# Sheet1.net
KiCad netlist of a schematic drawn in Altium Designer
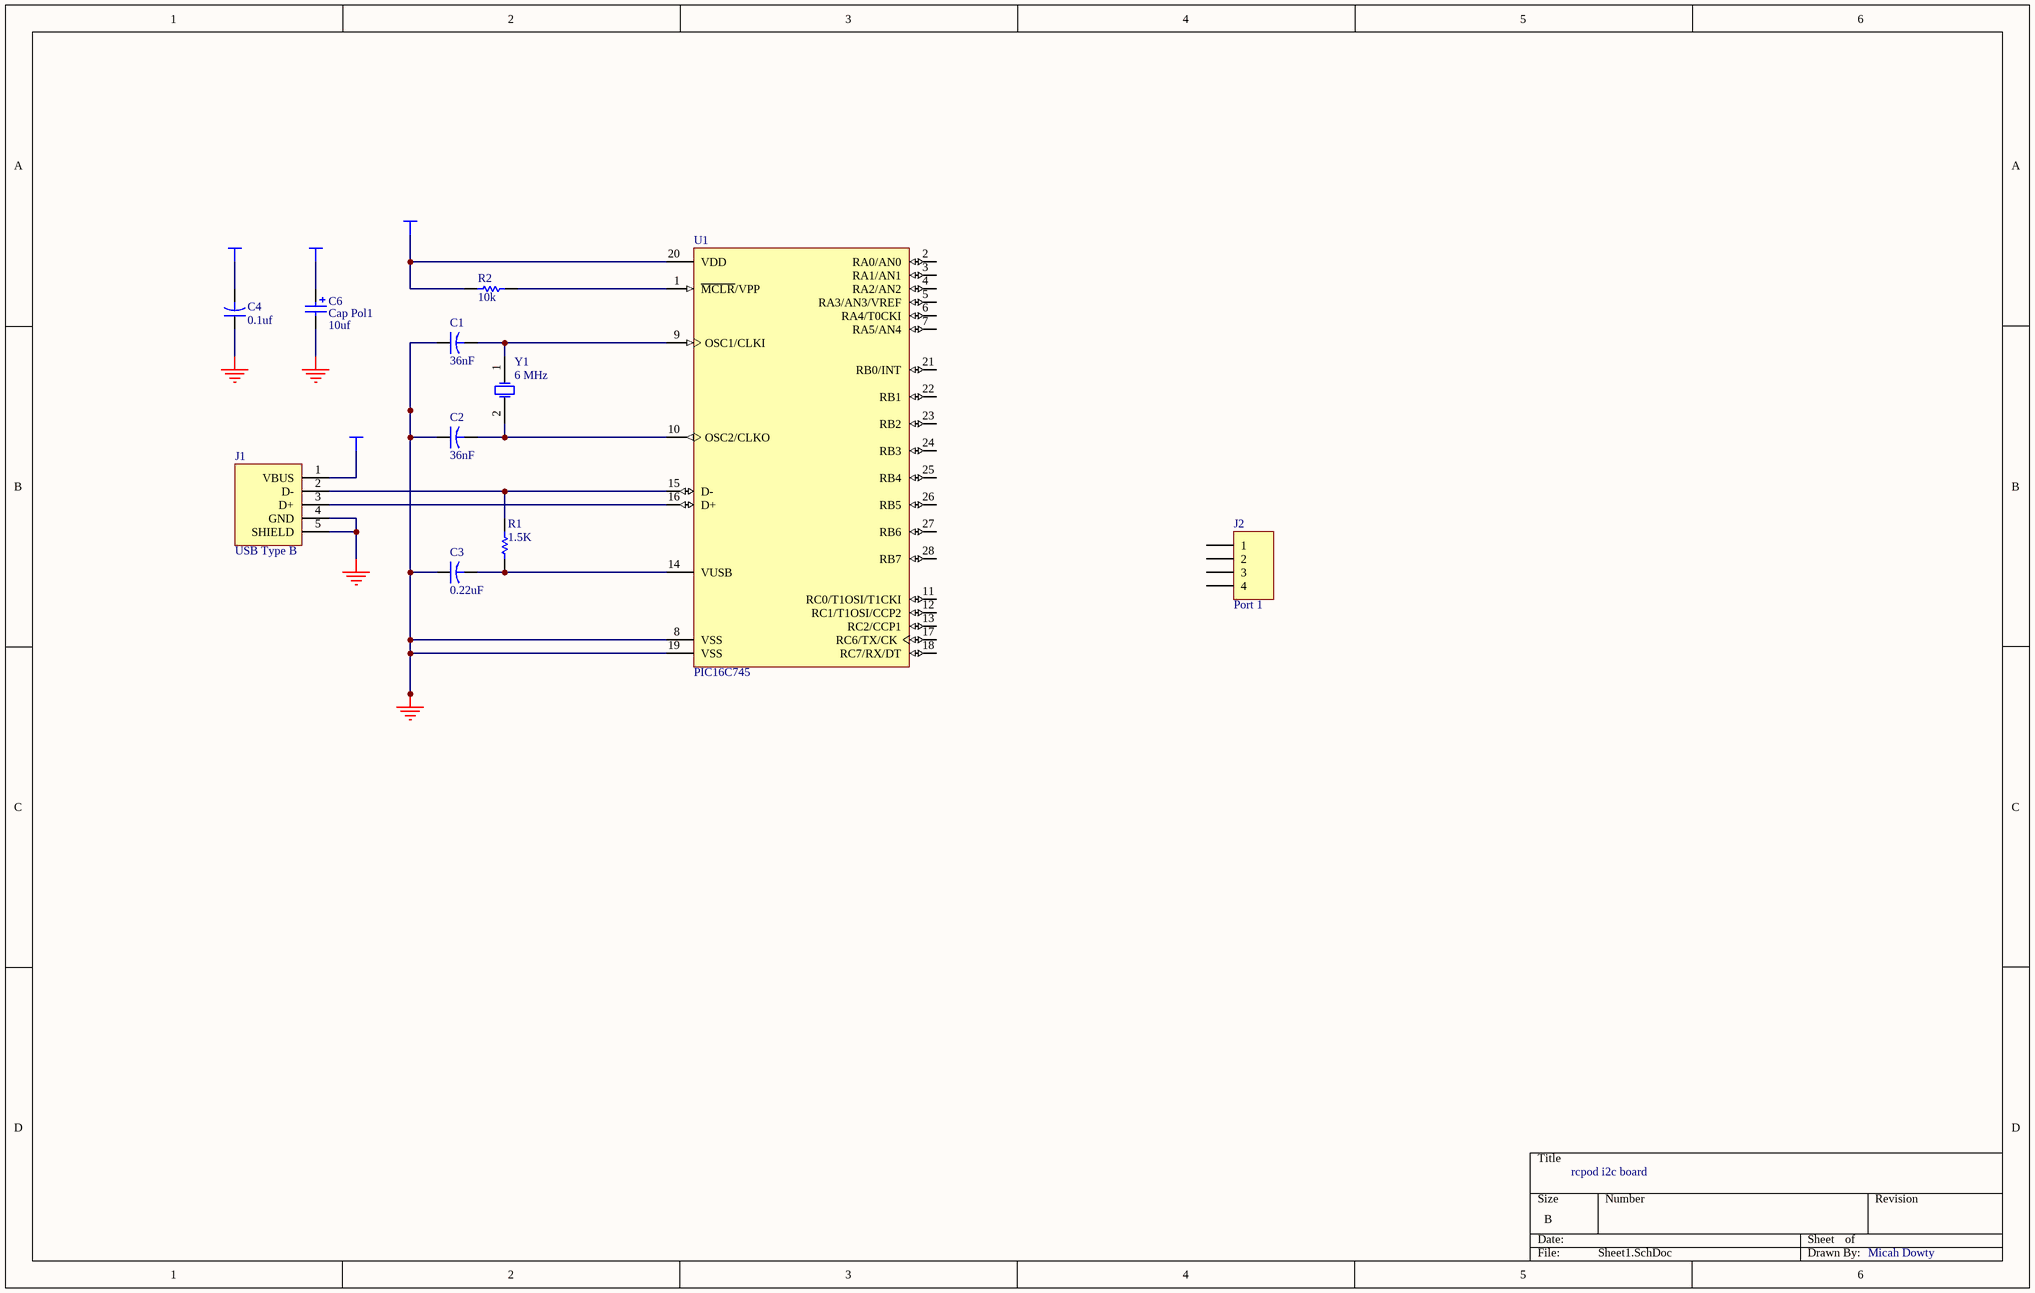
[diagram p0: Sheet1.SchDoc]

(export (version "E")
  (design (tool "Eeschema 10.0.6"))
  (components
    (comp (ref "C1")
      (value "Cap2")
      (footprint "CAPR5-4X5")
      (description "Capacitor")
      (fields
        (field (name "MANUFACTURER") "Generic Components")
        (field (name "ALTIUM_VALUE") "36nF")
        (field (name "PUBLISHER") "Altium Limited")
      )
      (libsource (lib "Miscellaneous Devices") (part "Cap2"))
    )
    (comp (ref "C2")
      (value "Cap2")
      (footprint "CAPR5-4X5")
      (description "Capacitor")
      (fields
        (field (name "MANUFACTURER") "Generic Components")
        (field (name "ALTIUM_VALUE") "36nF")
        (field (name "PUBLISHER") "Altium Limited")
      )
      (libsource (lib "Miscellaneous Devices") (part "Cap2"))
    )
    (comp (ref "C3")
      (value "0.22uF")
      (footprint "CAPR5-4X5")
      (description "Capacitor")
      (fields (field (name "MANUFACTURER") "Generic Components") (field (name "PUBLISHER") "Altium Limited"))
      (libsource (lib "Miscellaneous Devices") (part "Cap2"))
    )
    (comp (ref "C4")
      (value "0.1uf")
      (footprint "CAPR5-4X5")
      (description "Capacitor")
      (fields (field (name "MANUFACTURER") "Generic Components") (field (name "PUBLISHER") "Altium Limited"))
      (libsource (lib "Miscellaneous Devices") (part "Cap2"))
    )
    (comp (ref "C6")
      (value "Cap Pol1")
      (footprint "CAP-EE-1")
      (description "Polarized Capacitor (Radial)")
      (fields
        (field (name "MANUFACTURER") "Generic Components")
        (field (name "ALTIUM_VALUE") "10uf")
        (field (name "PUBLISHER") "Altium Limited")
      )
      (libsource (lib "Miscellaneous Devices") (part "Cap Pol1"))
    )
    (comp (ref "J1")
      (value "USB")
      (footprint "USB-TYPEB")
      (description "Header, 4-Pin")
      (fields (field (name "MANUFACTURER") "Generic Components") (field (name "PUBLISHER") "Altium Limited"))
      (libsource (lib "parts") (part "USB Type B"))
    )
    (comp (ref "J2")
      (value "Port 1")
      (footprint "HDR1X4")
      (description "Header, 4-Pin")
      (fields (field (name "MANUFACTURER") "Generic Components") (field (name "PUBLISHER") "Altium Limited"))
      (libsource (lib "Miscellaneous Connectors") (part "Header 4"))
    )
    (comp (ref "R1")
      (value "Res1")
      (footprint "AXIAL-0.3")
      (description "Resistor")
      (fields
        (field (name "MANUFACTURER") "Generic Components")
        (field (name "ALTIUM_VALUE") "1.5K")
        (field (name "PUBLISHER") "Altium Limited")
      )
      (libsource (lib "Miscellaneous Devices") (part "Res1"))
    )
    (comp (ref "R2")
      (value "Res1")
      (footprint "AXIAL-0.3")
      (description "Resistor")
      (fields
        (field (name "MANUFACTURER") "Generic Components")
        (field (name "ALTIUM_VALUE") "10k")
        (field (name "PUBLISHER") "Altium Limited")
      )
      (libsource (lib "Miscellaneous Devices") (part "Res1"))
    )
    (comp (ref "U1")
      (value "~")
      (footprint "DIP-28")
      (description "EPROM-Based 8-Bit CMOS Microcontroller with USB")
      (fields (field (name "MANUFACTURER") "Microchip"))
      (libsource (lib "parts") (part "PIC16C745"))
    )
    (comp (ref "Y1")
      (value "6 MHz")
      (footprint "BCY-W2/E4.7")
      (description "Crystal Oscillator")
      (fields (field (name "MANUFACTURER") "Generic Components") (field (name "PUBLISHER") "Altium Limited"))
      (libsource (lib "Miscellaneous Devices") (part "XTAL"))
    )
  )
  (nets
    (net (code "1") (name "GND") (class "Default")
      (node (ref "C1") (pin "1") (pinfunction "1_1") (pintype "passive"))
      (node (ref "C2") (pin "1") (pinfunction "1_1") (pintype "passive"))
      (node (ref "C3") (pin "1") (pinfunction "1_1") (pintype "passive"))
      (node (ref "C4") (pin "1") (pinfunction "1_1") (pintype "passive"))
      (node (ref "C6") (pin "2") (pinfunction "2_2") (pintype "passive"))
      (node (ref "J1") (pin "4") (pinfunction "GND_4") (pintype "passive"))
      (node (ref "J1") (pin "5") (pinfunction "SHIELD_5") (pintype "power_in"))
      (node (ref "U1") (pin "19") (pinfunction "VSS_19") (pintype "power_in"))
      (node (ref "U1") (pin "8") (pinfunction "VSS_8") (pintype "power_in"))
    )
    (net (code "2") (name "Net-(J1-D+)") (class "Default")
      (node (ref "J1") (pin "3") (pinfunction "D+_3") (pintype "passive"))
      (node (ref "U1") (pin "16") (pinfunction "D+_16") (pintype "bidirectional"))
    )
    (net (code "3") (name "Net-(J1-D-)") (class "Default")
      (node (ref "J1") (pin "2") (pinfunction "D-_2") (pintype "passive"))
      (node (ref "R1") (pin "2") (pinfunction "2_2") (pintype "passive"))
      (node (ref "U1") (pin "15") (pinfunction "D-_15") (pintype "bidirectional"))
    )
    (net (code "4") (name "Net-(U1-OSC1{slash}CLKI)") (class "Default")
      (node (ref "C1") (pin "2") (pinfunction "2_2") (pintype "passive"))
      (node (ref "U1") (pin "9") (pinfunction "OSC1/CLKI_9") (pintype "input"))
      (node (ref "Y1") (pin "1") (pinfunction "OSC1_1") (pintype "passive"))
    )
    (net (code "5") (name "Net-(U1-OSC2{slash}CLKO)") (class "Default")
      (node (ref "C2") (pin "2") (pinfunction "2_2") (pintype "passive"))
      (node (ref "U1") (pin "10") (pinfunction "OSC2/CLKO_10") (pintype "output"))
      (node (ref "Y1") (pin "2") (pinfunction "OSC2_2") (pintype "passive"))
    )
    (net (code "6") (name "Net-(U1-VUSB)") (class "Default")
      (node (ref "C3") (pin "2") (pinfunction "2_2") (pintype "passive"))
      (node (ref "R1") (pin "1") (pinfunction "1_1") (pintype "passive"))
      (node (ref "U1") (pin "14") (pinfunction "VUSB_14") (pintype "power_in"))
    )
    (net (code "7") (name "Net-(U1-~{MCLR}{slash}VPP)") (class "Default")
      (node (ref "R2") (pin "1") (pinfunction "1_1") (pintype "passive"))
      (node (ref "U1") (pin "1") (pinfunction "~{MCLR}/VPP_1") (pintype "input"))
    )
    (net (code "8") (name "VCC") (class "Default")
      (node (ref "C4") (pin "2") (pinfunction "2_2") (pintype "passive"))
      (node (ref "C6") (pin "1") (pinfunction "1_1") (pintype "passive"))
      (node (ref "J1") (pin "1") (pinfunction "VBUS_1") (pintype "passive"))
      (node (ref "R2") (pin "2") (pinfunction "2_2") (pintype "passive"))
      (node (ref "U1") (pin "20") (pinfunction "VDD_20") (pintype "power_in"))
    )
    (net (code "9") (name "unconnected-(J2-Pad1)") (class "Default")
      (node (ref "J2") (pin "1") (pinfunction "1_1") (pintype "passive"))
    )
    (net (code "10") (name "unconnected-(J2-Pad2)") (class "Default")
      (node (ref "J2") (pin "2") (pinfunction "2_2") (pintype "passive"))
    )
    (net (code "11") (name "unconnected-(J2-Pad3)") (class "Default")
      (node (ref "J2") (pin "3") (pinfunction "3_3") (pintype "passive"))
    )
    (net (code "12") (name "unconnected-(J2-Pad4)") (class "Default")
      (node (ref "J2") (pin "4") (pinfunction "4_4") (pintype "passive"))
    )
    (net (code "13") (name "unconnected-(U1-RA0{slash}AN0-Pad2)") (class "Default")
      (node (ref "U1") (pin "2") (pinfunction "RA0/AN0_2") (pintype "bidirectional"))
    )
    (net (code "14") (name "unconnected-(U1-RA1{slash}AN1-Pad3)") (class "Default")
      (node (ref "U1") (pin "3") (pinfunction "RA1/AN1_3") (pintype "bidirectional"))
    )
    (net (code "15") (name "unconnected-(U1-RA2{slash}AN2-Pad4)") (class "Default")
      (node (ref "U1") (pin "4") (pinfunction "RA2/AN2_4") (pintype "bidirectional"))
    )
    (net (code "16") (name "unconnected-(U1-RA3{slash}AN3{slash}VREF-Pad5)") (class "Default")
      (node (ref "U1") (pin "5") (pinfunction "RA3/AN3/VREF_5") (pintype "bidirectional"))
    )
    (net (code "17") (name "unconnected-(U1-RA4{slash}T0CKI-Pad6)") (class "Default")
      (node (ref "U1") (pin "6") (pinfunction "RA4/T0CKI_6") (pintype "bidirectional"))
    )
    (net (code "18") (name "unconnected-(U1-RA5{slash}AN4-Pad7)") (class "Default")
      (node (ref "U1") (pin "7") (pinfunction "RA5/AN4_7") (pintype "bidirectional"))
    )
    (net (code "19") (name "unconnected-(U1-RB0{slash}INT-Pad21)") (class "Default")
      (node (ref "U1") (pin "21") (pinfunction "RB0/INT_21") (pintype "bidirectional"))
    )
    (net (code "20") (name "unconnected-(U1-RB1-Pad22)") (class "Default")
      (node (ref "U1") (pin "22") (pinfunction "RB1_22") (pintype "bidirectional"))
    )
    (net (code "21") (name "unconnected-(U1-RB2-Pad23)") (class "Default")
      (node (ref "U1") (pin "23") (pinfunction "RB2_23") (pintype "bidirectional"))
    )
    (net (code "22") (name "unconnected-(U1-RB3-Pad24)") (class "Default")
      (node (ref "U1") (pin "24") (pinfunction "RB3_24") (pintype "bidirectional"))
    )
    (net (code "23") (name "unconnected-(U1-RB4-Pad25)") (class "Default")
      (node (ref "U1") (pin "25") (pinfunction "RB4_25") (pintype "bidirectional"))
    )
    (net (code "24") (name "unconnected-(U1-RB5-Pad26)") (class "Default")
      (node (ref "U1") (pin "26") (pinfunction "RB5_26") (pintype "bidirectional"))
    )
    (net (code "25") (name "unconnected-(U1-RB6-Pad27)") (class "Default")
      (node (ref "U1") (pin "27") (pinfunction "RB6_27") (pintype "bidirectional"))
    )
    (net (code "26") (name "unconnected-(U1-RB7-Pad28)") (class "Default")
      (node (ref "U1") (pin "28") (pinfunction "RB7_28") (pintype "bidirectional"))
    )
    (net (code "27") (name "unconnected-(U1-RC0{slash}T1OSI{slash}T1CKI-Pad11)") (class "Default")
      (node (ref "U1") (pin "11") (pinfunction "RC0/T1OSI/T1CKI_11") (pintype "bidirectional"))
    )
    (net (code "28") (name "unconnected-(U1-RC1{slash}T1OSI{slash}CCP2-Pad12)") (class "Default")
      (node (ref "U1") (pin "12") (pinfunction "RC1/T1OSI/CCP2_12") (pintype "bidirectional"))
    )
    (net (code "29") (name "unconnected-(U1-RC2{slash}CCP1-Pad13)") (class "Default")
      (node (ref "U1") (pin "13") (pinfunction "RC2/CCP1_13") (pintype "bidirectional"))
    )
    (net (code "30") (name "unconnected-(U1-RC6{slash}TX{slash}CK-Pad17)") (class "Default")
      (node (ref "U1") (pin "17") (pinfunction "RC6/TX/CK_17") (pintype "bidirectional"))
    )
    (net (code "31") (name "unconnected-(U1-RC7{slash}RX{slash}DT-Pad18)") (class "Default")
      (node (ref "U1") (pin "18") (pinfunction "RC7/RX/DT_18") (pintype "bidirectional"))
    )
  )
)
